# microscope_slide_LED.net
KiCad netlist of a schematic drawn in EAGLE
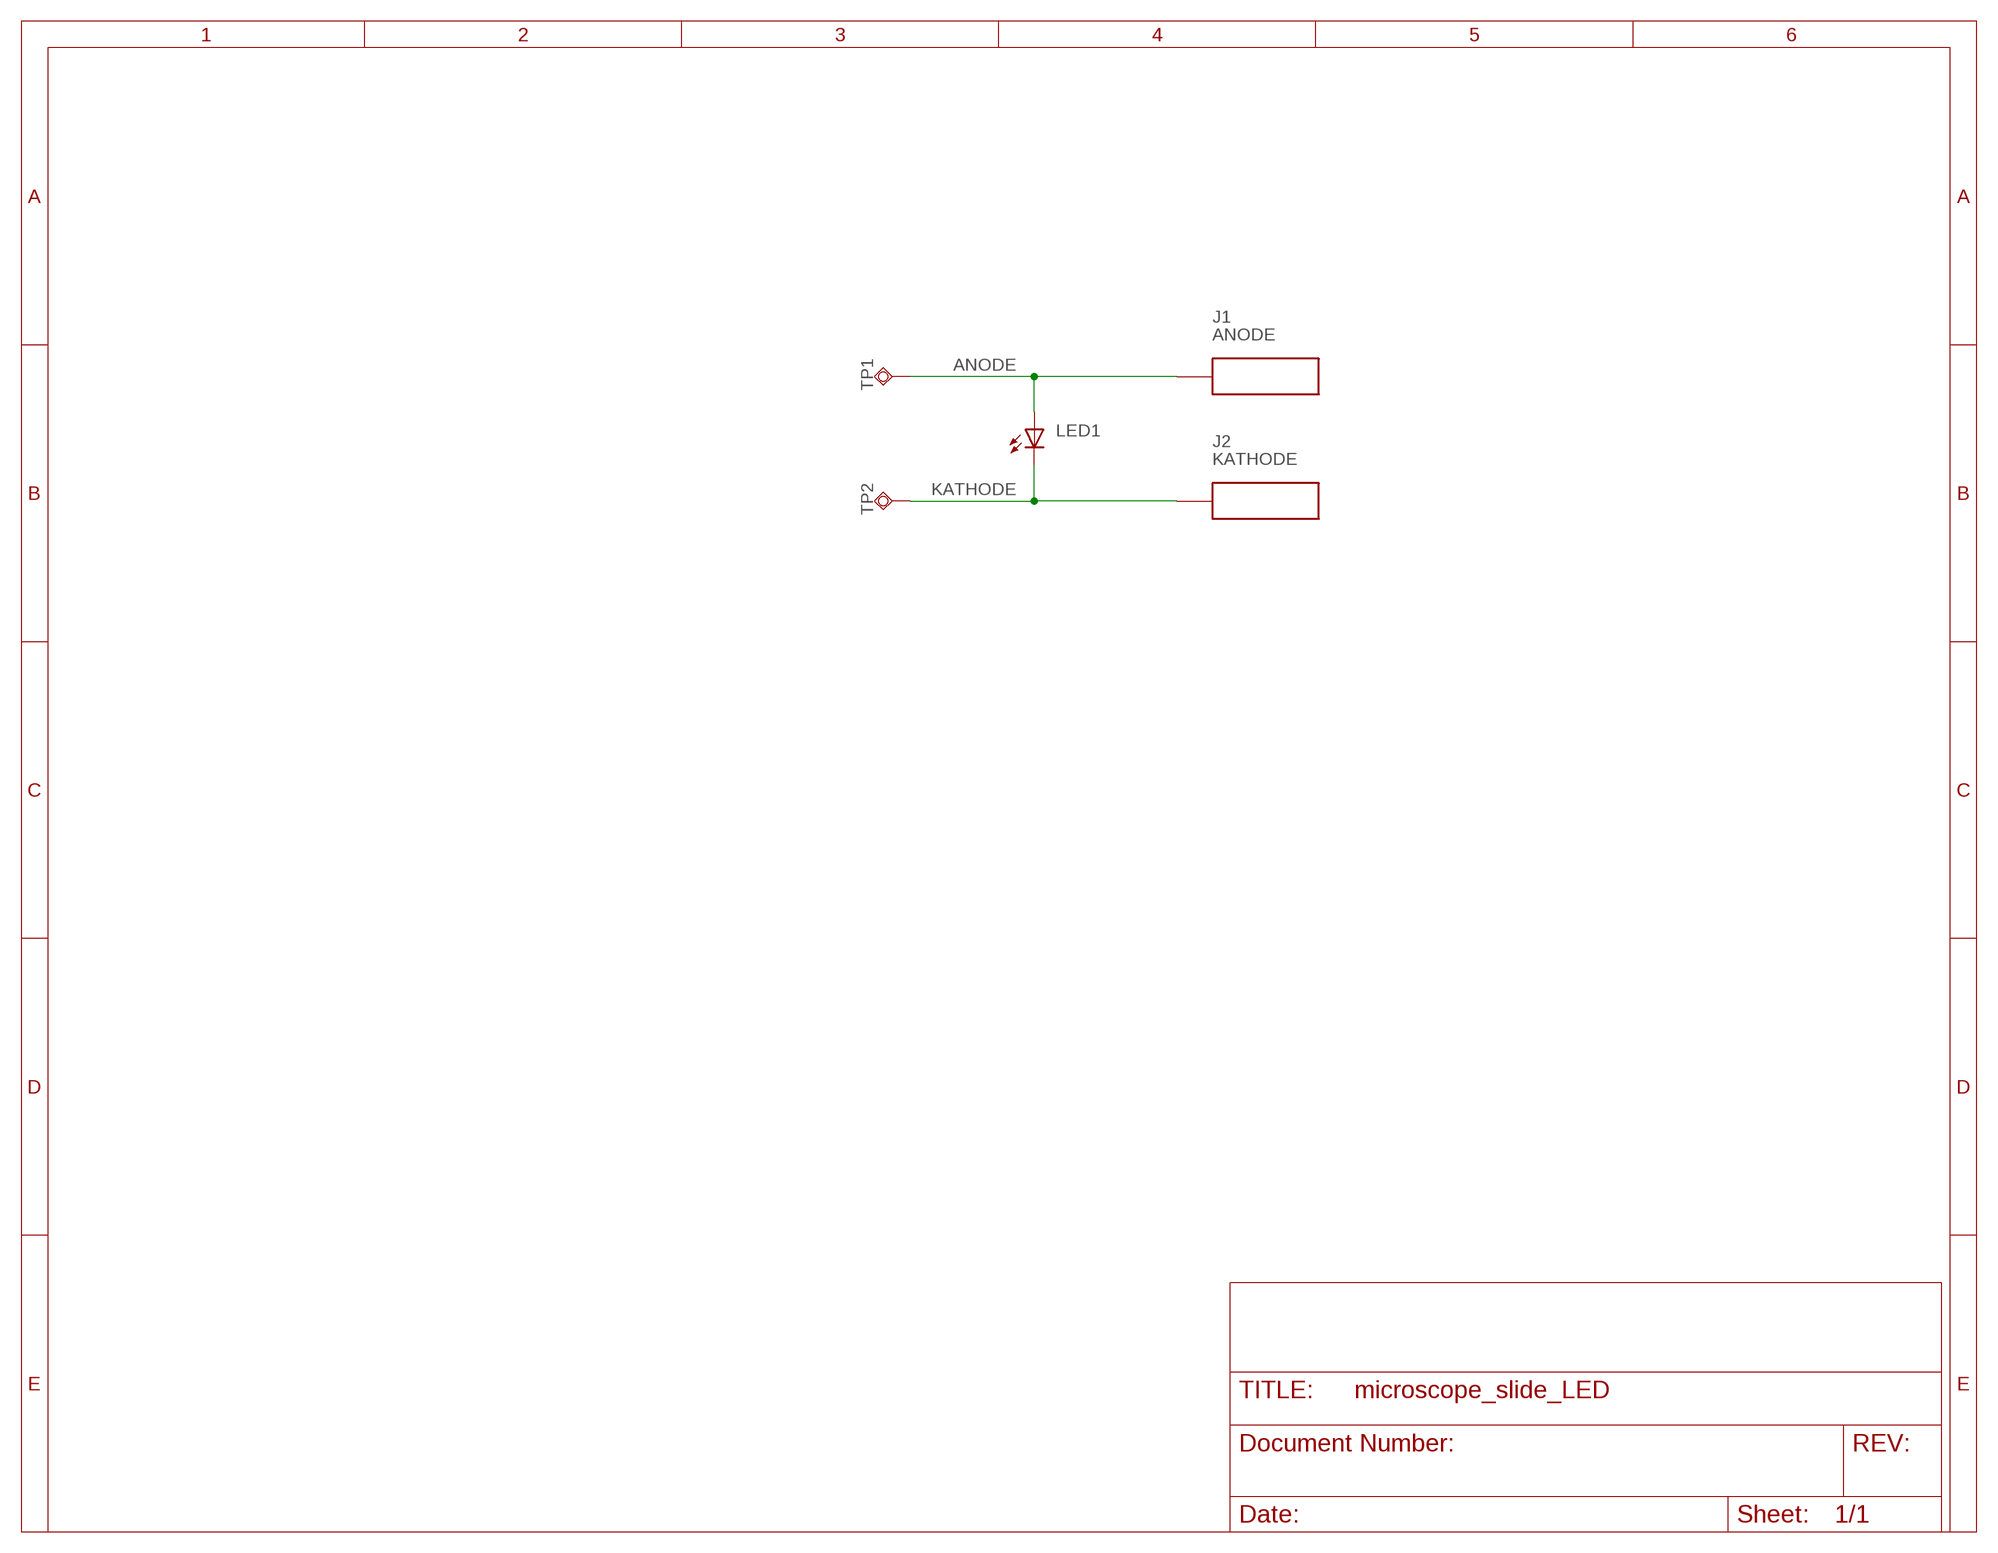
[diagram p0: schematic, sheet 1]

(export (version "E")
  (design (tool "Eeschema 10.0.6"))
  (components
    (comp (ref "J1")
      (value "ANODE")
      (footprint "eagle-import:0.125_PAD")
      (libsource (lib "eagle-import") (part "0.125_PAD"))
    )
    (comp (ref "J2")
      (value "KATHODE")
      (footprint "eagle-import:0.125_PAD")
      (libsource (lib "eagle-import") (part "0.125_PAD"))
    )
    (comp (ref "LED1")
      (value "LEDCHIPLED_0603")
      (footprint "eagle-import:CHIPLED_0603")
      (libsource (lib "eagle-import") (part "LEDCHIPLED_0603"))
    )
    (comp (ref "TP1")
      (value "ANODE")
      (footprint "eagle-import:TP20SQ")
      (libsource (lib "eagle-import") (part "TPSQTP20SQ"))
    )
    (comp (ref "TP2")
      (value "KATHODE")
      (footprint "eagle-import:TP20SQ")
      (libsource (lib "eagle-import") (part "TPSQTP20SQ"))
    )
  )
  (nets
    (net (code "1") (name "/ANODE") (class "Default")
      (node (ref "J1") (pin "1") (pinfunction "1_1") (pintype "bidirectional"))
      (node (ref "LED1") (pin "A") (pinfunction "A_A") (pintype "passive"))
      (node (ref "TP1") (pin "TP") (pinfunction "TP_TP") (pintype "input"))
    )
    (net (code "2") (name "/KATHODE") (class "Default")
      (node (ref "J2") (pin "1") (pinfunction "1_1") (pintype "bidirectional"))
      (node (ref "LED1") (pin "C") (pinfunction "C_C") (pintype "passive"))
      (node (ref "TP2") (pin "TP") (pinfunction "TP_TP") (pintype "input"))
    )
  )
)
